# Debugger.net
KiCad netlist of a schematic drawn in EAGLE
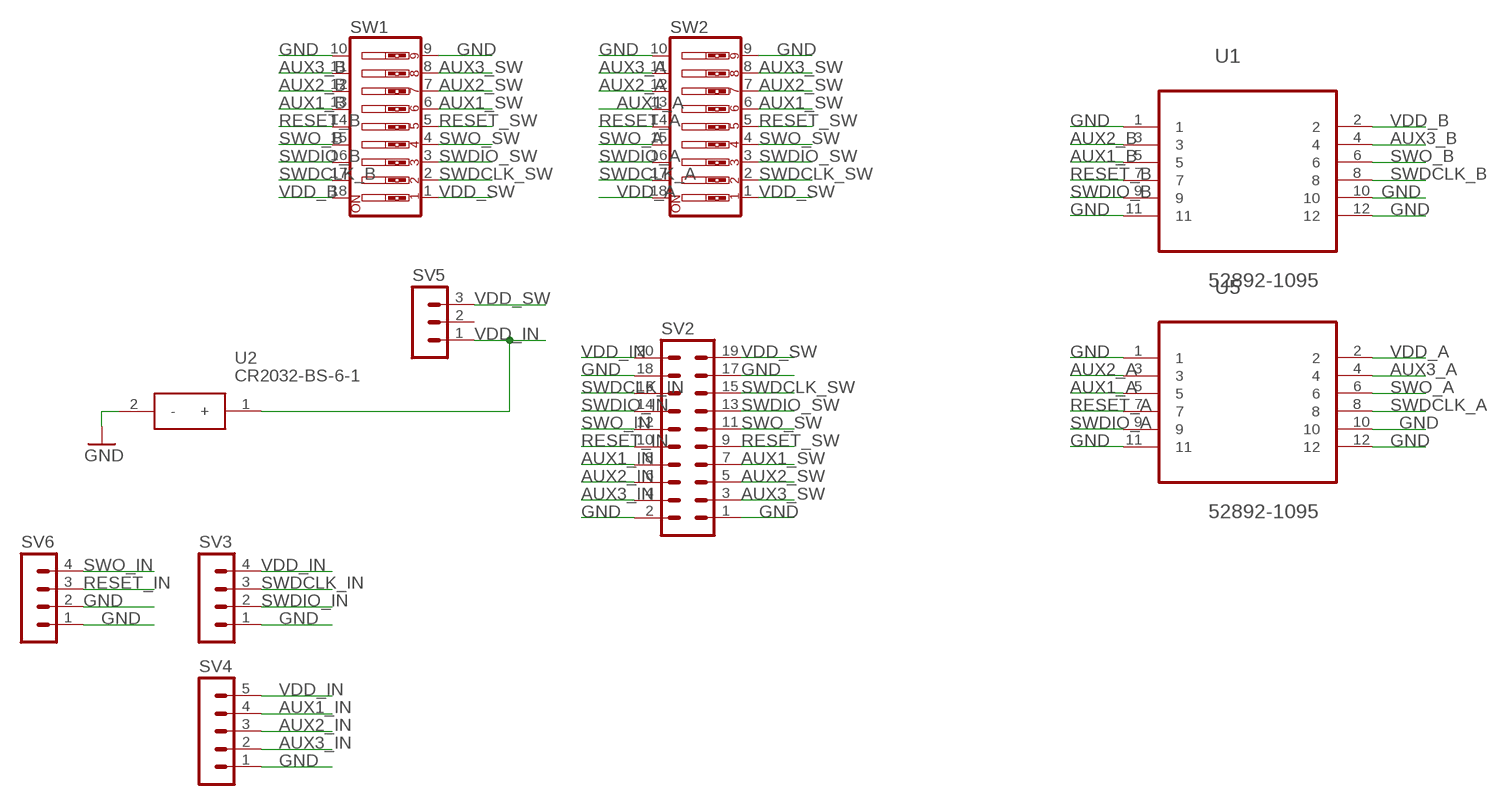
[diagram p0: schematic, sheet 1]

(export (version "E")
  (design (tool "Eeschema 10.0.6"))
  (components
    (comp (ref "SV2")
      (value "MA10-2")
      (footprint "eagle-import:MA10-2")
      (libsource (lib "eagle-import") (part "MA10-2"))
    )
    (comp (ref "SV3")
      (value "MA04-1")
      (footprint "eagle-import:MA04-1")
      (libsource (lib "eagle-import") (part "MA04-1"))
    )
    (comp (ref "SV4")
      (value "MA05-1")
      (footprint "eagle-import:MA05-1")
      (libsource (lib "eagle-import") (part "MA05-1"))
    )
    (comp (ref "SV5")
      (value "MA03-1")
      (footprint "eagle-import:MA03-1")
      (libsource (lib "eagle-import") (part "MA03-1"))
    )
    (comp (ref "SV6")
      (value "MA04-1")
      (footprint "eagle-import:MA04-1")
      (libsource (lib "eagle-import") (part "MA04-1"))
    )
    (comp (ref "SW1")
      (value "SW_DIP-9")
      (footprint "eagle-import:EDG-09")
      (libsource (lib "eagle-import") (part "SW_DIP-9"))
    )
    (comp (ref "SW2")
      (value "SW_DIP-9")
      (footprint "eagle-import:EDG-09")
      (libsource (lib "eagle-import") (part "SW_DIP-9"))
    )
    (comp (ref "U1")
      (value "52892-1095")
      (footprint "eagle-import:MOLEX_52892-1095")
      (fields (field (name "MF") "Molex"))
      (libsource (lib "eagle-import") (part "52892-1095"))
    )
    (comp (ref "U2")
      (value "CR2032-BS-6-1")
      (footprint "eagle-import:CR2032BS61")
      (libsource (lib "eagle-import") (part "CR2032-BS-6-1"))
    )
    (comp (ref "U5")
      (value "52892-1095")
      (footprint "eagle-import:MOLEX_52892-1095")
      (fields (field (name "MF") "Molex"))
      (libsource (lib "eagle-import") (part "52892-1095"))
    )
  )
  (nets
    (net (code "1") (name "/AUX1_A") (class "Default")
      (node (ref "SW2") (pin "13") (pinfunction "13_13") (pintype "passive"))
      (node (ref "U5") (pin "5") (pinfunction "5_5") (pintype "passive"))
    )
    (net (code "2") (name "/AUX1_B") (class "Default")
      (node (ref "SW1") (pin "13") (pinfunction "13_13") (pintype "passive"))
      (node (ref "U1") (pin "5") (pinfunction "5_5") (pintype "passive"))
    )
    (net (code "3") (name "/AUX1_IN") (class "Default")
      (node (ref "SV2") (pin "8") (pinfunction "8_8") (pintype "passive"))
      (node (ref "SV4") (pin "4") (pinfunction "4_4") (pintype "passive"))
    )
    (net (code "4") (name "/AUX1_SW") (class "Default")
      (node (ref "SV2") (pin "7") (pinfunction "7_7") (pintype "passive"))
      (node (ref "SW1") (pin "6") (pinfunction "6_6") (pintype "passive"))
      (node (ref "SW2") (pin "6") (pinfunction "6_6") (pintype "passive"))
    )
    (net (code "5") (name "/AUX2_A") (class "Default")
      (node (ref "SW2") (pin "12") (pinfunction "12_12") (pintype "passive"))
      (node (ref "U5") (pin "3") (pinfunction "3_3") (pintype "passive"))
    )
    (net (code "6") (name "/AUX2_B") (class "Default")
      (node (ref "SW1") (pin "12") (pinfunction "12_12") (pintype "passive"))
      (node (ref "U1") (pin "3") (pinfunction "3_3") (pintype "passive"))
    )
    (net (code "7") (name "/AUX2_IN") (class "Default")
      (node (ref "SV2") (pin "6") (pinfunction "6_6") (pintype "passive"))
      (node (ref "SV4") (pin "3") (pinfunction "3_3") (pintype "passive"))
    )
    (net (code "8") (name "/AUX2_SW") (class "Default")
      (node (ref "SV2") (pin "5") (pinfunction "5_5") (pintype "passive"))
      (node (ref "SW1") (pin "7") (pinfunction "7_7") (pintype "passive"))
      (node (ref "SW2") (pin "7") (pinfunction "7_7") (pintype "passive"))
    )
    (net (code "9") (name "/AUX3_A") (class "Default")
      (node (ref "SW2") (pin "11") (pinfunction "11_11") (pintype "passive"))
      (node (ref "U5") (pin "4") (pinfunction "4_4") (pintype "passive"))
    )
    (net (code "10") (name "/AUX3_B") (class "Default")
      (node (ref "SW1") (pin "11") (pinfunction "11_11") (pintype "passive"))
      (node (ref "U1") (pin "4") (pinfunction "4_4") (pintype "passive"))
    )
    (net (code "11") (name "/AUX3_IN") (class "Default")
      (node (ref "SV2") (pin "4") (pinfunction "4_4") (pintype "passive"))
      (node (ref "SV4") (pin "2") (pinfunction "2_2") (pintype "passive"))
    )
    (net (code "12") (name "/AUX3_SW") (class "Default")
      (node (ref "SV2") (pin "3") (pinfunction "3_3") (pintype "passive"))
      (node (ref "SW1") (pin "8") (pinfunction "8_8") (pintype "passive"))
      (node (ref "SW2") (pin "8") (pinfunction "8_8") (pintype "passive"))
    )
    (net (code "13") (name "/RESET_A") (class "Default")
      (node (ref "SW2") (pin "14") (pinfunction "14_14") (pintype "passive"))
      (node (ref "U5") (pin "7") (pinfunction "7_7") (pintype "passive"))
    )
    (net (code "14") (name "/RESET_B") (class "Default")
      (node (ref "SW1") (pin "14") (pinfunction "14_14") (pintype "passive"))
      (node (ref "U1") (pin "7") (pinfunction "7_7") (pintype "passive"))
    )
    (net (code "15") (name "/RESET_IN") (class "Default")
      (node (ref "SV2") (pin "10") (pinfunction "10_10") (pintype "passive"))
      (node (ref "SV6") (pin "3") (pinfunction "3_3") (pintype "passive"))
    )
    (net (code "16") (name "/RESET_SW") (class "Default")
      (node (ref "SV2") (pin "9") (pinfunction "9_9") (pintype "passive"))
      (node (ref "SW1") (pin "5") (pinfunction "5_5") (pintype "passive"))
      (node (ref "SW2") (pin "5") (pinfunction "5_5") (pintype "passive"))
    )
    (net (code "17") (name "/SWDCLK_A") (class "Default")
      (node (ref "SW2") (pin "17") (pinfunction "17_17") (pintype "passive"))
      (node (ref "U5") (pin "8") (pinfunction "8_8") (pintype "passive"))
    )
    (net (code "18") (name "/SWDCLK_B") (class "Default")
      (node (ref "SW1") (pin "17") (pinfunction "17_17") (pintype "passive"))
      (node (ref "U1") (pin "8") (pinfunction "8_8") (pintype "passive"))
    )
    (net (code "19") (name "/SWDCLK_IN") (class "Default")
      (node (ref "SV2") (pin "16") (pinfunction "16_16") (pintype "passive"))
      (node (ref "SV3") (pin "3") (pinfunction "3_3") (pintype "passive"))
    )
    (net (code "20") (name "/SWDCLK_SW") (class "Default")
      (node (ref "SV2") (pin "15") (pinfunction "15_15") (pintype "passive"))
      (node (ref "SW1") (pin "2") (pinfunction "2_2") (pintype "passive"))
      (node (ref "SW2") (pin "2") (pinfunction "2_2") (pintype "passive"))
    )
    (net (code "21") (name "/SWDIO_A") (class "Default")
      (node (ref "SW2") (pin "16") (pinfunction "16_16") (pintype "passive"))
      (node (ref "U5") (pin "9") (pinfunction "9_9") (pintype "passive"))
    )
    (net (code "22") (name "/SWDIO_B") (class "Default")
      (node (ref "SW1") (pin "16") (pinfunction "16_16") (pintype "passive"))
      (node (ref "U1") (pin "9") (pinfunction "9_9") (pintype "passive"))
    )
    (net (code "23") (name "/SWDIO_IN") (class "Default")
      (node (ref "SV2") (pin "14") (pinfunction "14_14") (pintype "passive"))
      (node (ref "SV3") (pin "2") (pinfunction "2_2") (pintype "passive"))
    )
    (net (code "24") (name "/SWDIO_SW") (class "Default")
      (node (ref "SV2") (pin "13") (pinfunction "13_13") (pintype "passive"))
      (node (ref "SW1") (pin "3") (pinfunction "3_3") (pintype "passive"))
      (node (ref "SW2") (pin "3") (pinfunction "3_3") (pintype "passive"))
    )
    (net (code "25") (name "/SWO_A") (class "Default")
      (node (ref "SW2") (pin "15") (pinfunction "15_15") (pintype "passive"))
      (node (ref "U5") (pin "6") (pinfunction "6_6") (pintype "passive"))
    )
    (net (code "26") (name "/SWO_B") (class "Default")
      (node (ref "SW1") (pin "15") (pinfunction "15_15") (pintype "passive"))
      (node (ref "U1") (pin "6") (pinfunction "6_6") (pintype "passive"))
    )
    (net (code "27") (name "/SWO_IN") (class "Default")
      (node (ref "SV2") (pin "12") (pinfunction "12_12") (pintype "passive"))
      (node (ref "SV6") (pin "4") (pinfunction "4_4") (pintype "passive"))
    )
    (net (code "28") (name "/SWO_SW") (class "Default")
      (node (ref "SV2") (pin "11") (pinfunction "11_11") (pintype "passive"))
      (node (ref "SW1") (pin "4") (pinfunction "4_4") (pintype "passive"))
      (node (ref "SW2") (pin "4") (pinfunction "4_4") (pintype "passive"))
    )
    (net (code "29") (name "/VDD_A") (class "Default")
      (node (ref "SW2") (pin "18") (pinfunction "18_18") (pintype "passive"))
      (node (ref "U5") (pin "2") (pinfunction "2_2") (pintype "passive"))
    )
    (net (code "30") (name "/VDD_B") (class "Default")
      (node (ref "SW1") (pin "18") (pinfunction "18_18") (pintype "passive"))
      (node (ref "U1") (pin "2") (pinfunction "2_2") (pintype "passive"))
    )
    (net (code "31") (name "/VDD_IN") (class "Default")
      (node (ref "SV2") (pin "20") (pinfunction "20_20") (pintype "passive"))
      (node (ref "SV3") (pin "4") (pinfunction "4_4") (pintype "passive"))
      (node (ref "SV4") (pin "5") (pinfunction "5_5") (pintype "passive"))
      (node (ref "SV5") (pin "1") (pinfunction "1_1") (pintype "passive"))
      (node (ref "U2") (pin "1") (pinfunction "+_1") (pintype "bidirectional"))
    )
    (net (code "32") (name "/VDD_SW") (class "Default")
      (node (ref "SV2") (pin "19") (pinfunction "19_19") (pintype "passive"))
      (node (ref "SV5") (pin "3") (pinfunction "3_3") (pintype "passive"))
      (node (ref "SW1") (pin "1") (pinfunction "1_1") (pintype "passive"))
      (node (ref "SW2") (pin "1") (pinfunction "1_1") (pintype "passive"))
    )
    (net (code "33") (name "GND") (class "Default")
      (node (ref "SV2") (pin "1") (pinfunction "1_1") (pintype "passive"))
      (node (ref "SV2") (pin "17") (pinfunction "17_17") (pintype "passive"))
      (node (ref "SV2") (pin "18") (pinfunction "18_18") (pintype "passive"))
      (node (ref "SV2") (pin "2") (pinfunction "2_2") (pintype "passive"))
      (node (ref "SV3") (pin "1") (pinfunction "1_1") (pintype "passive"))
      (node (ref "SV4") (pin "1") (pinfunction "1_1") (pintype "passive"))
      (node (ref "SV6") (pin "1") (pinfunction "1_1") (pintype "passive"))
      (node (ref "SV6") (pin "2") (pinfunction "2_2") (pintype "passive"))
      (node (ref "SW1") (pin "10") (pinfunction "10_10") (pintype "passive"))
      (node (ref "SW1") (pin "9") (pinfunction "9_9") (pintype "passive"))
      (node (ref "SW2") (pin "10") (pinfunction "10_10") (pintype "passive"))
      (node (ref "SW2") (pin "9") (pinfunction "9_9") (pintype "passive"))
      (node (ref "U1") (pin "1") (pinfunction "1_1") (pintype "passive"))
      (node (ref "U1") (pin "10") (pinfunction "10_10") (pintype "passive"))
      (node (ref "U1") (pin "11") (pinfunction "11_11") (pintype "passive"))
      (node (ref "U1") (pin "12") (pinfunction "12_12") (pintype "passive"))
      (node (ref "U2") (pin "2") (pinfunction "-_2") (pintype "bidirectional"))
      (node (ref "U5") (pin "1") (pinfunction "1_1") (pintype "passive"))
      (node (ref "U5") (pin "10") (pinfunction "10_10") (pintype "passive"))
      (node (ref "U5") (pin "11") (pinfunction "11_11") (pintype "passive"))
      (node (ref "U5") (pin "12") (pinfunction "12_12") (pintype "passive"))
    )
    (net (code "34") (name "unconnected-(SV5-Pad2)") (class "Default")
      (node (ref "SV5") (pin "2") (pinfunction "2_2") (pintype "passive"))
    )
  )
)
